# DRAM_DDR4_Bank_2_Connector.net
KiCad netlist of a schematic drawn in Altium Designer
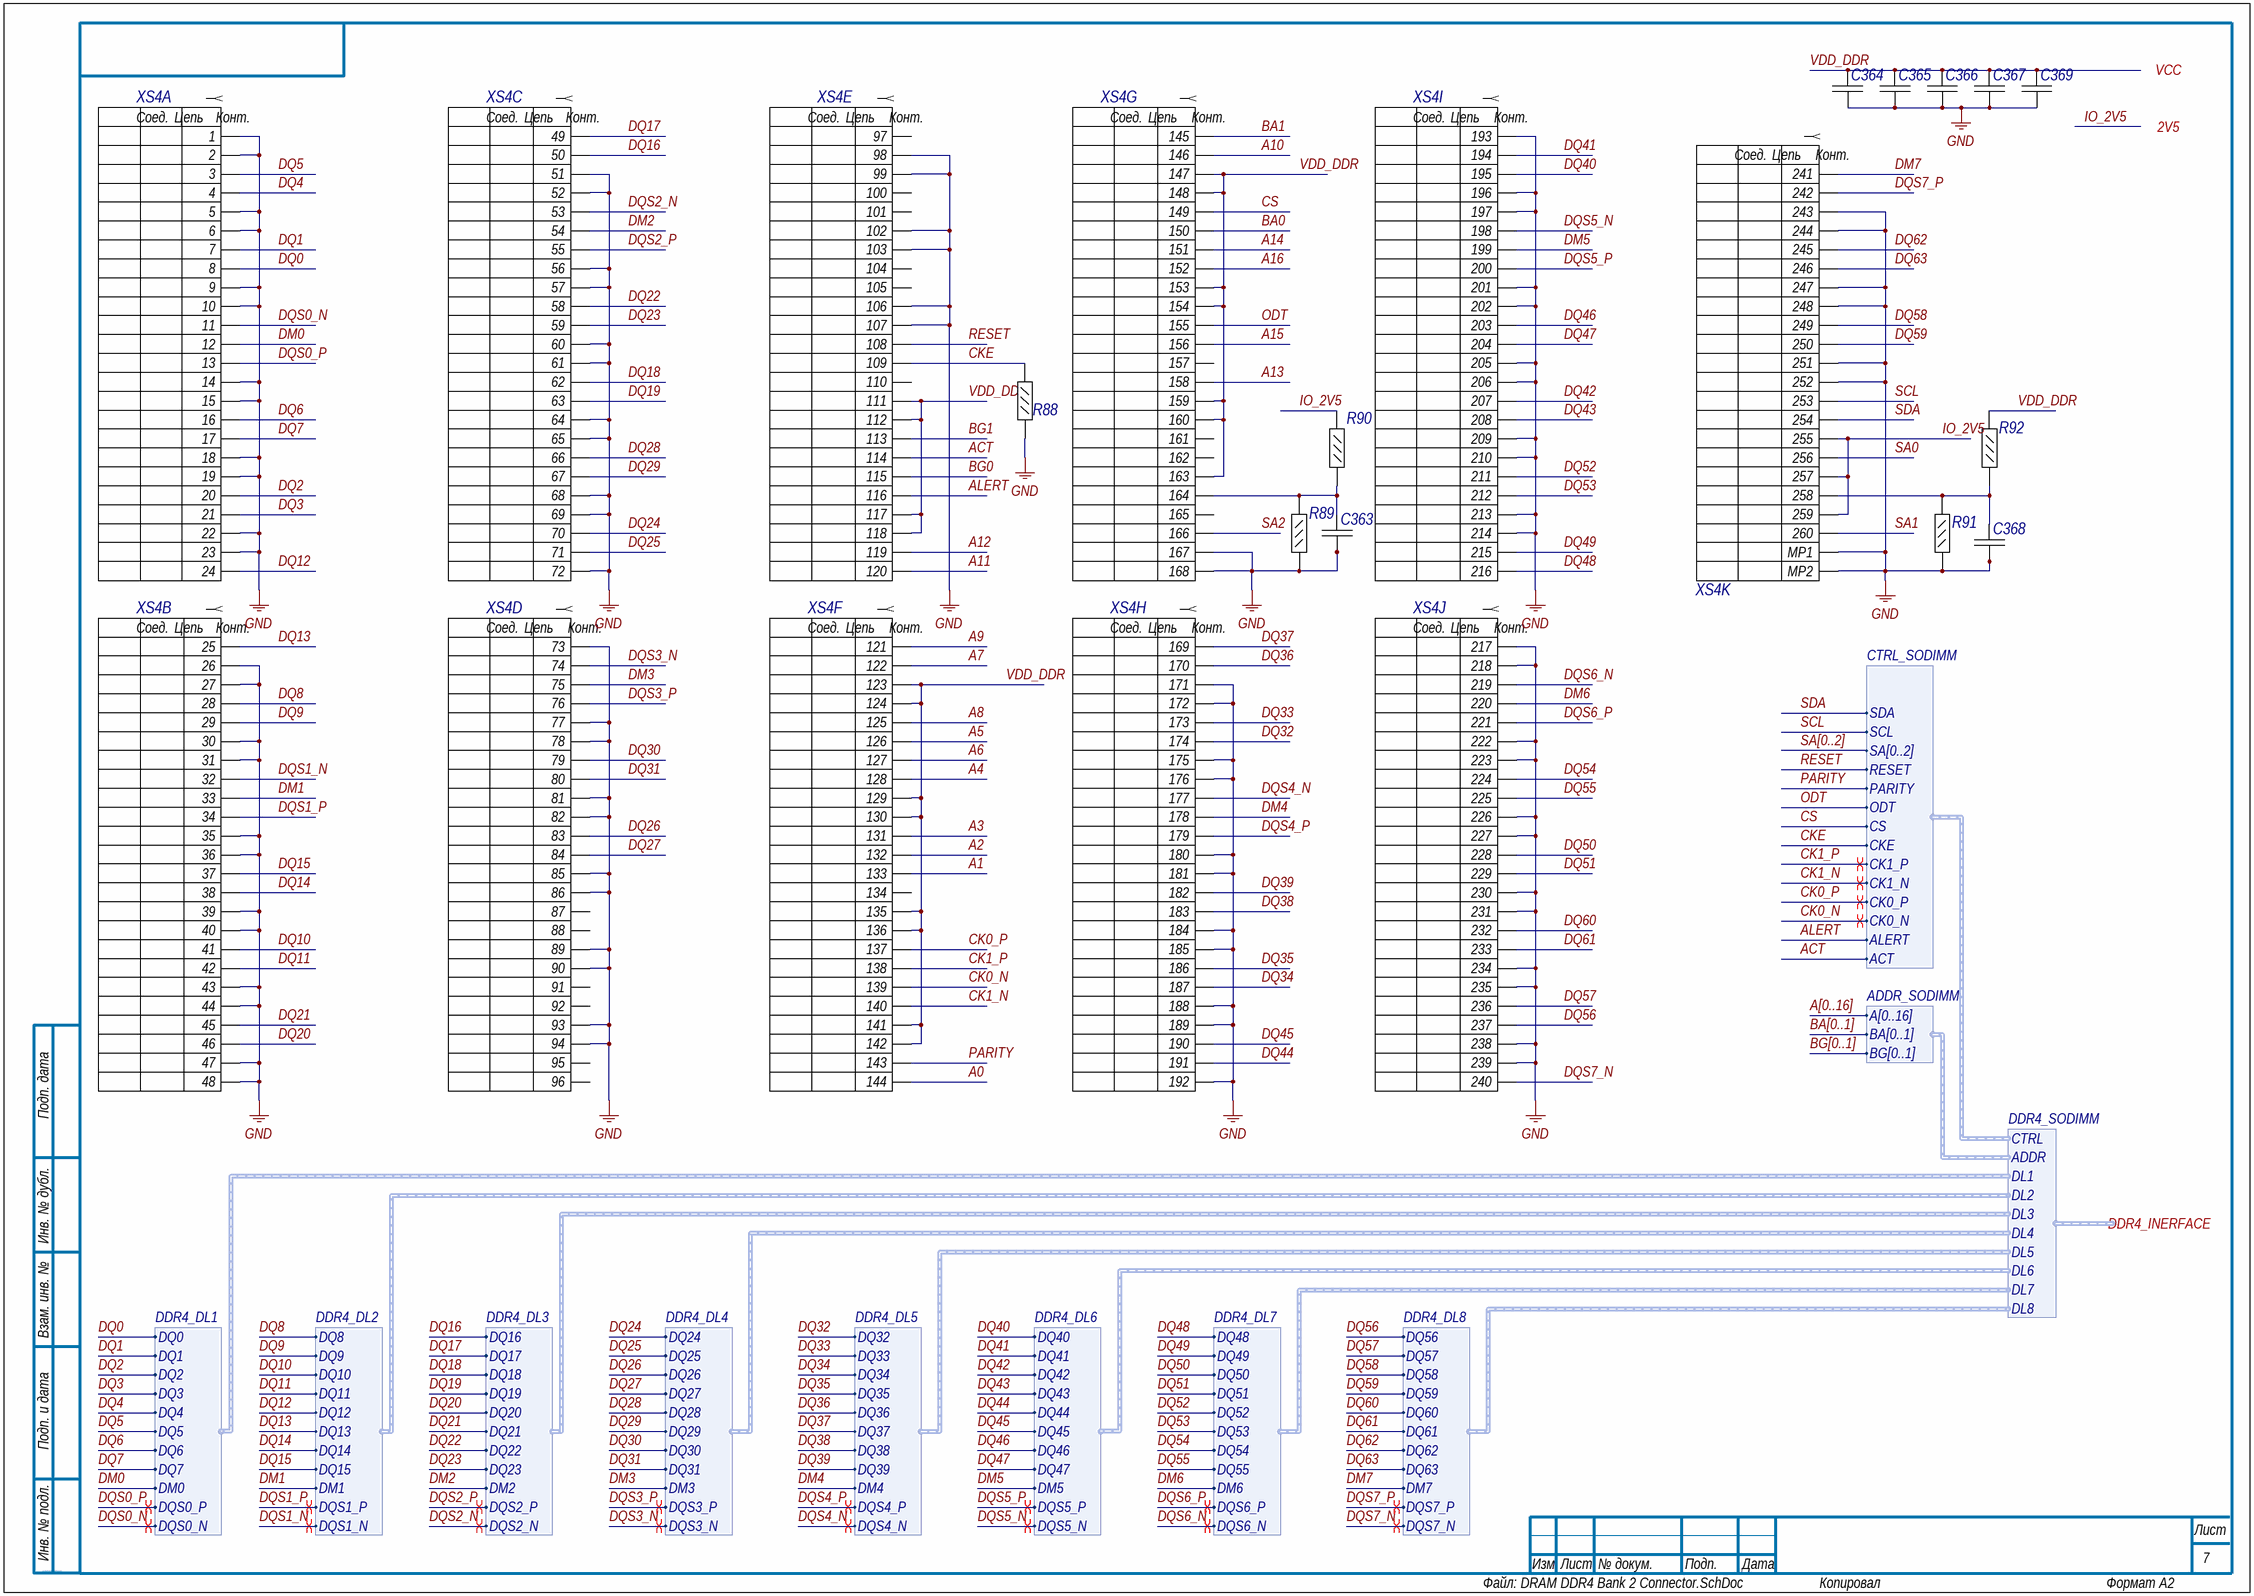
[diagram p0: DRAM DDR4 Bank 2 Connector.SchDoc]

(export (version "E")
  (design (tool "Eeschema 10.0.6"))
  (components
    (comp (ref "C363")
      (value "C1005X7R1E104M")
      (footprint "CAPC1005X55X10LL05")
      (description "Chip Capacitor, 0.1 uF, +/- 20%, 25 V, -55 to 125 degC, 0402 (1005 Metric), RoHS, Tape and Reel")
      (fields (field (name "TOLERANCE") "20%"))
      (libsource (lib "MiniPC DB") (part "CAP_NP"))
    )
    (comp (ref "C364")
      (value "C1005X7R1E104M")
      (footprint "CAPC1005X55X10LL05")
      (description "Chip Capacitor, 0.1 uF, +/- 20%, 25 V, -55 to 125 degC, 0402 (1005 Metric), RoHS, Tape and Reel")
      (fields (field (name "TOLERANCE") "20%"))
      (libsource (lib "MiniPC DB") (part "CAP_NP"))
    )
    (comp (ref "C365")
      (value "C1005X7R1E104M")
      (footprint "CAPC1005X55X10LL05")
      (description "Chip Capacitor, 0.1 uF, +/- 20%, 25 V, -55 to 125 degC, 0402 (1005 Metric), RoHS, Tape and Reel")
      (fields (field (name "TOLERANCE") "20%"))
      (libsource (lib "MiniPC DB") (part "CAP_NP"))
    )
    (comp (ref "C366")
      (value "C1005X7R1E104M")
      (footprint "CAPC1005X55X10LL05")
      (description "Chip Capacitor, 0.1 uF, +/- 20%, 25 V, -55 to 125 degC, 0402 (1005 Metric), RoHS, Tape and Reel")
      (fields (field (name "TOLERANCE") "20%"))
      (libsource (lib "MiniPC DB") (part "CAP_NP"))
    )
    (comp (ref "C367")
      (value "C1005X7R1E104M")
      (footprint "CAPC1005X55X10LL05")
      (description "Chip Capacitor, 0.1 uF, +/- 20%, 25 V, -55 to 125 degC, 0402 (1005 Metric), RoHS, Tape and Reel")
      (fields (field (name "TOLERANCE") "20%"))
      (libsource (lib "MiniPC DB") (part "CAP_NP"))
    )
    (comp (ref "C368")
      (value "C1005X7R1E104M")
      (footprint "CAPC1005X55X10LL05")
      (description "Chip Capacitor, 0.1 uF, +/- 20%, 25 V, -55 to 125 degC, 0402 (1005 Metric), RoHS, Tape and Reel")
      (fields (field (name "TOLERANCE") "20%"))
      (libsource (lib "MiniPC DB") (part "CAP_NP"))
    )
    (comp (ref "C369")
      (value "C1005X7R1E104M")
      (footprint "CAPC1005X55X10LL05")
      (description "Chip Capacitor, 0.1 uF, +/- 20%, 25 V, -55 to 125 degC, 0402 (1005 Metric), RoHS, Tape and Reel")
      (fields (field (name "TOLERANCE") "20%"))
      (libsource (lib "MiniPC DB") (part "CAP_NP"))
    )
    (comp (ref "R88")
      (value "RC0402JR-0739RL")
      (footprint "RESC1005X40X25LL05T05")
      (description "Chip Resistor, 39 Ohm, +/- 5%, 0.063 W, -55 to 155 degC, 0402 (1005 Metric), RoHS, Tape and Reel")
      (fields (field (name "TOLERANCE") "5%"))
      (libsource (lib "MiniPC DB") (part "RES-0.05"))
    )
    (comp (ref "R89")
      (value "RC0402JR-0739RL")
      (footprint "RESC1005X40X25LL05T05")
      (description "Chip Resistor, 39 Ohm, +/- 5%, 0.063 W, -55 to 155 degC, 0402 (1005 Metric), RoHS, Tape and Reel")
      (fields (field (name "TOLERANCE") "5%"))
      (libsource (lib "") (part "RES-0.05_1"))
    )
    (comp (ref "R90")
      (value "RC0402JR-0739RL")
      (footprint "RESC1005X40X25LL05T05")
      (description "Chip Resistor, 39 Ohm, +/- 5%, 0.063 W, -55 to 155 degC, 0402 (1005 Metric), RoHS, Tape and Reel")
      (fields (field (name "TOLERANCE") "5%"))
      (libsource (lib "") (part "RES-0.05_2"))
    )
    (comp (ref "R91")
      (value "RC0402JR-0739RL")
      (footprint "RESC1005X40X25LL05T05")
      (description "Chip Resistor, 39 Ohm, +/- 5%, 0.063 W, -55 to 155 degC, 0402 (1005 Metric), RoHS, Tape and Reel")
      (fields (field (name "TOLERANCE") "5%"))
      (libsource (lib "") (part "RES-0.05_1"))
    )
    (comp (ref "R92")
      (value "RC0402JR-0739RL")
      (footprint "RESC1005X40X25LL05T05")
      (description "Chip Resistor, 39 Ohm, +/- 5%, 0.063 W, -55 to 155 degC, 0402 (1005 Metric), RoHS, Tape and Reel")
      (fields (field (name "TOLERANCE") "5%"))
      (libsource (lib "") (part "RES-0.05_2"))
    )
    (comp (ref "XS4")
      (value "AS0A823-H4SB-7H")
      (footprint "FOXC-AS0A823-H4SB-7H_V")
      (libsource (lib "MiniPC DB") (part "ROZ_262K"))
    )
  )
  (nets
    (net (code "10") (name "/A0") (class "Default")
      (node (ref "XS4") (pin "144") (pinfunction "144_144") (pintype "passive"))
    )
    (net (code "11") (name "/A1") (class "Default")
      (node (ref "XS4") (pin "133") (pinfunction "133_133") (pintype "passive"))
    )
    (net (code "12") (name "/A2") (class "Default")
      (node (ref "XS4") (pin "132") (pinfunction "132_132") (pintype "passive"))
    )
    (net (code "13") (name "/A3") (class "Default")
      (node (ref "XS4") (pin "131") (pinfunction "131_131") (pintype "passive"))
    )
    (net (code "14") (name "/A4") (class "Default")
      (node (ref "XS4") (pin "128") (pinfunction "128_128") (pintype "passive"))
    )
    (net (code "15") (name "/A5") (class "Default")
      (node (ref "XS4") (pin "126") (pinfunction "126_126") (pintype "passive"))
    )
    (net (code "16") (name "/A6") (class "Default")
      (node (ref "XS4") (pin "127") (pinfunction "127_127") (pintype "passive"))
    )
    (net (code "17") (name "/A7") (class "Default")
      (node (ref "XS4") (pin "122") (pinfunction "122_122") (pintype "passive"))
    )
    (net (code "18") (name "/A8") (class "Default")
      (node (ref "XS4") (pin "125") (pinfunction "125_125") (pintype "passive"))
    )
    (net (code "19") (name "/A9") (class "Default")
      (node (ref "XS4") (pin "121") (pinfunction "121_121") (pintype "passive"))
    )
    (net (code "20") (name "/A10") (class "Default")
      (node (ref "XS4") (pin "146") (pinfunction "146_146") (pintype "passive"))
    )
    (net (code "21") (name "/A11") (class "Default")
      (node (ref "XS4") (pin "120") (pinfunction "120_120") (pintype "passive"))
    )
    (net (code "22") (name "/A12") (class "Default")
      (node (ref "XS4") (pin "119") (pinfunction "119_119") (pintype "passive"))
    )
    (net (code "23") (name "/A13") (class "Default")
      (node (ref "XS4") (pin "158") (pinfunction "158_158") (pintype "passive"))
    )
    (net (code "24") (name "/A14") (class "Default")
      (node (ref "XS4") (pin "151") (pinfunction "151_151") (pintype "passive"))
    )
    (net (code "25") (name "/A15") (class "Default")
      (node (ref "XS4") (pin "156") (pinfunction "156_156") (pintype "passive"))
    )
    (net (code "26") (name "/A16") (class "Default")
      (node (ref "XS4") (pin "152") (pinfunction "152_152") (pintype "passive"))
    )
    (net (code "27") (name "/ACT") (class "Default")
      (node (ref "XS4") (pin "114") (pinfunction "114_114") (pintype "passive"))
    )
    (net (code "28") (name "/ALERT") (class "Default")
      (node (ref "XS4") (pin "116") (pinfunction "116_116") (pintype "passive"))
    )
    (net (code "30") (name "/BA0") (class "Default")
      (node (ref "XS4") (pin "150") (pinfunction "150_150") (pintype "passive"))
    )
    (net (code "31") (name "/BA1") (class "Default")
      (node (ref "XS4") (pin "145") (pinfunction "145_145") (pintype "passive"))
    )
    (net (code "33") (name "/BG0") (class "Default")
      (node (ref "XS4") (pin "115") (pinfunction "115_115") (pintype "passive"))
    )
    (net (code "34") (name "/BG1") (class "Default")
      (node (ref "XS4") (pin "113") (pinfunction "113_113") (pintype "passive"))
    )
    (net (code "35") (name "/CK0_N") (class "Default")
      (node (ref "XS4") (pin "139") (pinfunction "139_139") (pintype "passive"))
    )
    (net (code "36") (name "/CK0_P") (class "Default")
      (node (ref "XS4") (pin "137") (pinfunction "137_137") (pintype "passive"))
    )
    (net (code "37") (name "/CK1_N") (class "Default")
      (node (ref "XS4") (pin "140") (pinfunction "140_140") (pintype "passive"))
    )
    (net (code "38") (name "/CK1_P") (class "Default")
      (node (ref "XS4") (pin "138") (pinfunction "138_138") (pintype "passive"))
    )
    (net (code "39") (name "/CKE") (class "Default")
      (node (ref "R88") (pin "2") (pinfunction "2_2") (pintype "passive"))
      (node (ref "XS4") (pin "109") (pinfunction "109_109") (pintype "passive"))
    )
    (net (code "40") (name "/CS") (class "Default")
      (node (ref "XS4") (pin "149") (pinfunction "149_149") (pintype "passive"))
    )
    (net (code "42") (name "/DM0") (class "Default")
      (node (ref "XS4") (pin "12") (pinfunction "12_12") (pintype "passive"))
    )
    (net (code "43") (name "/DM1") (class "Default")
      (node (ref "XS4") (pin "33") (pinfunction "33_33") (pintype "passive"))
    )
    (net (code "44") (name "/DM2") (class "Default")
      (node (ref "XS4") (pin "54") (pinfunction "54_54") (pintype "passive"))
    )
    (net (code "45") (name "/DM3") (class "Default")
      (node (ref "XS4") (pin "75") (pinfunction "75_75") (pintype "passive"))
    )
    (net (code "46") (name "/DM4") (class "Default")
      (node (ref "XS4") (pin "178") (pinfunction "178_178") (pintype "passive"))
    )
    (net (code "47") (name "/DM5") (class "Default")
      (node (ref "XS4") (pin "199") (pinfunction "199_199") (pintype "passive"))
    )
    (net (code "48") (name "/DM6") (class "Default")
      (node (ref "XS4") (pin "220") (pinfunction "220_220") (pintype "passive"))
    )
    (net (code "49") (name "/DM7") (class "Default")
      (node (ref "XS4") (pin "241") (pinfunction "241_241") (pintype "passive"))
    )
    (net (code "50") (name "/DQ0") (class "Default")
      (node (ref "XS4") (pin "8") (pinfunction "8_8") (pintype "passive"))
    )
    (net (code "51") (name "/DQ1") (class "Default")
      (node (ref "XS4") (pin "7") (pinfunction "7_7") (pintype "passive"))
    )
    (net (code "52") (name "/DQ2") (class "Default")
      (node (ref "XS4") (pin "20") (pinfunction "20_20") (pintype "passive"))
    )
    (net (code "53") (name "/DQ3") (class "Default")
      (node (ref "XS4") (pin "21") (pinfunction "21_21") (pintype "passive"))
    )
    (net (code "54") (name "/DQ4") (class "Default")
      (node (ref "XS4") (pin "4") (pinfunction "4_4") (pintype "passive"))
    )
    (net (code "55") (name "/DQ5") (class "Default")
      (node (ref "XS4") (pin "3") (pinfunction "3_3") (pintype "passive"))
    )
    (net (code "56") (name "/DQ6") (class "Default")
      (node (ref "XS4") (pin "16") (pinfunction "16_16") (pintype "passive"))
    )
    (net (code "57") (name "/DQ7") (class "Default")
      (node (ref "XS4") (pin "17") (pinfunction "17_17") (pintype "passive"))
    )
    (net (code "58") (name "/DQ8") (class "Default")
      (node (ref "XS4") (pin "28") (pinfunction "28_28") (pintype "passive"))
    )
    (net (code "59") (name "/DQ9") (class "Default")
      (node (ref "XS4") (pin "29") (pinfunction "29_29") (pintype "passive"))
    )
    (net (code "60") (name "/DQ10") (class "Default")
      (node (ref "XS4") (pin "41") (pinfunction "41_41") (pintype "passive"))
    )
    (net (code "61") (name "/DQ11") (class "Default")
      (node (ref "XS4") (pin "42") (pinfunction "42_42") (pintype "passive"))
    )
    (net (code "62") (name "/DQ12") (class "Default")
      (node (ref "XS4") (pin "24") (pinfunction "24_24") (pintype "passive"))
    )
    (net (code "63") (name "/DQ13") (class "Default")
      (node (ref "XS4") (pin "25") (pinfunction "25_25") (pintype "passive"))
    )
    (net (code "64") (name "/DQ14") (class "Default")
      (node (ref "XS4") (pin "38") (pinfunction "38_38") (pintype "passive"))
    )
    (net (code "65") (name "/DQ15") (class "Default")
      (node (ref "XS4") (pin "37") (pinfunction "37_37") (pintype "passive"))
    )
    (net (code "66") (name "/DQ16") (class "Default")
      (node (ref "XS4") (pin "50") (pinfunction "50_50") (pintype "passive"))
    )
    (net (code "67") (name "/DQ17") (class "Default")
      (node (ref "XS4") (pin "49") (pinfunction "49_49") (pintype "passive"))
    )
    (net (code "68") (name "/DQ18") (class "Default")
      (node (ref "XS4") (pin "62") (pinfunction "62_62") (pintype "passive"))
    )
    (net (code "69") (name "/DQ19") (class "Default")
      (node (ref "XS4") (pin "63") (pinfunction "63_63") (pintype "passive"))
    )
    (net (code "70") (name "/DQ20") (class "Default")
      (node (ref "XS4") (pin "46") (pinfunction "46_46") (pintype "passive"))
    )
    (net (code "71") (name "/DQ21") (class "Default")
      (node (ref "XS4") (pin "45") (pinfunction "45_45") (pintype "passive"))
    )
    (net (code "72") (name "/DQ22") (class "Default")
      (node (ref "XS4") (pin "58") (pinfunction "58_58") (pintype "passive"))
    )
    (net (code "73") (name "/DQ23") (class "Default")
      (node (ref "XS4") (pin "59") (pinfunction "59_59") (pintype "passive"))
    )
    (net (code "74") (name "/DQ24") (class "Default")
      (node (ref "XS4") (pin "70") (pinfunction "70_70") (pintype "passive"))
    )
    (net (code "75") (name "/DQ25") (class "Default")
      (node (ref "XS4") (pin "71") (pinfunction "71_71") (pintype "passive"))
    )
    (net (code "76") (name "/DQ26") (class "Default")
      (node (ref "XS4") (pin "83") (pinfunction "83_83") (pintype "passive"))
    )
    (net (code "77") (name "/DQ27") (class "Default")
      (node (ref "XS4") (pin "84") (pinfunction "84_84") (pintype "passive"))
    )
    (net (code "78") (name "/DQ28") (class "Default")
      (node (ref "XS4") (pin "66") (pinfunction "66_66") (pintype "passive"))
    )
    (net (code "79") (name "/DQ29") (class "Default")
      (node (ref "XS4") (pin "67") (pinfunction "67_67") (pintype "passive"))
    )
    (net (code "80") (name "/DQ30") (class "Default")
      (node (ref "XS4") (pin "79") (pinfunction "79_79") (pintype "passive"))
    )
    (net (code "81") (name "/DQ31") (class "Default")
      (node (ref "XS4") (pin "80") (pinfunction "80_80") (pintype "passive"))
    )
    (net (code "82") (name "/DQ32") (class "Default")
      (node (ref "XS4") (pin "174") (pinfunction "174_174") (pintype "passive"))
    )
    (net (code "83") (name "/DQ33") (class "Default")
      (node (ref "XS4") (pin "173") (pinfunction "173_173") (pintype "passive"))
    )
    (net (code "84") (name "/DQ34") (class "Default")
      (node (ref "XS4") (pin "187") (pinfunction "187_187") (pintype "passive"))
    )
    (net (code "85") (name "/DQ35") (class "Default")
      (node (ref "XS4") (pin "186") (pinfunction "186_186") (pintype "passive"))
    )
    (net (code "86") (name "/DQ36") (class "Default")
      (node (ref "XS4") (pin "170") (pinfunction "170_170") (pintype "passive"))
    )
    (net (code "87") (name "/DQ37") (class "Default")
      (node (ref "XS4") (pin "169") (pinfunction "169_169") (pintype "passive"))
    )
    (net (code "88") (name "/DQ38") (class "Default")
      (node (ref "XS4") (pin "183") (pinfunction "183_183") (pintype "passive"))
    )
    (net (code "89") (name "/DQ39") (class "Default")
      (node (ref "XS4") (pin "182") (pinfunction "182_182") (pintype "passive"))
    )
    (net (code "90") (name "/DQ40") (class "Default")
      (node (ref "XS4") (pin "195") (pinfunction "195_195") (pintype "passive"))
    )
    (net (code "91") (name "/DQ41") (class "Default")
      (node (ref "XS4") (pin "194") (pinfunction "194_194") (pintype "passive"))
    )
    (net (code "92") (name "/DQ42") (class "Default")
      (node (ref "XS4") (pin "207") (pinfunction "207_207") (pintype "passive"))
    )
    (net (code "93") (name "/DQ43") (class "Default")
      (node (ref "XS4") (pin "208") (pinfunction "208_208") (pintype "passive"))
    )
    (net (code "94") (name "/DQ44") (class "Default")
      (node (ref "XS4") (pin "191") (pinfunction "191_191") (pintype "passive"))
    )
    (net (code "95") (name "/DQ45") (class "Default")
      (node (ref "XS4") (pin "190") (pinfunction "190_190") (pintype "passive"))
    )
    (net (code "96") (name "/DQ46") (class "Default")
      (node (ref "XS4") (pin "203") (pinfunction "203_203") (pintype "passive"))
    )
    (net (code "97") (name "/DQ47") (class "Default")
      (node (ref "XS4") (pin "204") (pinfunction "204_204") (pintype "passive"))
    )
    (net (code "98") (name "/DQ48") (class "Default")
      (node (ref "XS4") (pin "216") (pinfunction "216_216") (pintype "passive"))
    )
    (net (code "99") (name "/DQ49") (class "Default")
      (node (ref "XS4") (pin "215") (pinfunction "215_215") (pintype "passive"))
    )
    (net (code "100") (name "/DQ50") (class "Default")
      (node (ref "XS4") (pin "228") (pinfunction "228_228") (pintype "passive"))
    )
    (net (code "101") (name "/DQ51") (class "Default")
      (node (ref "XS4") (pin "229") (pinfunction "229_229") (pintype "passive"))
    )
    (net (code "102") (name "/DQ52") (class "Default")
      (node (ref "XS4") (pin "211") (pinfunction "211_211") (pintype "passive"))
    )
    (net (code "103") (name "/DQ53") (class "Default")
      (node (ref "XS4") (pin "212") (pinfunction "212_212") (pintype "passive"))
    )
    (net (code "104") (name "/DQ54") (class "Default")
      (node (ref "XS4") (pin "224") (pinfunction "224_224") (pintype "passive"))
    )
    (net (code "105") (name "/DQ55") (class "Default")
      (node (ref "XS4") (pin "225") (pinfunction "225_225") (pintype "passive"))
    )
    (net (code "106") (name "/DQ56") (class "Default")
      (node (ref "XS4") (pin "237") (pinfunction "237_237") (pintype "passive"))
    )
    (net (code "107") (name "/DQ57") (class "Default")
      (node (ref "XS4") (pin "236") (pinfunction "236_236") (pintype "passive"))
    )
    (net (code "108") (name "/DQ58") (class "Default")
      (node (ref "XS4") (pin "249") (pinfunction "249_249") (pintype "passive"))
    )
    (net (code "109") (name "/DQ59") (class "Default")
      (node (ref "XS4") (pin "250") (pinfunction "250_250") (pintype "passive"))
    )
    (net (code "110") (name "/DQ60") (class "Default")
      (node (ref "XS4") (pin "232") (pinfunction "232_232") (pintype "passive"))
    )
    (net (code "111") (name "/DQ61") (class "Default")
      (node (ref "XS4") (pin "233") (pinfunction "233_233") (pintype "passive"))
    )
    (net (code "112") (name "/DQ62") (class "Default")
      (node (ref "XS4") (pin "245") (pinfunction "245_245") (pintype "passive"))
    )
    (net (code "113") (name "/DQ63") (class "Default")
      (node (ref "XS4") (pin "246") (pinfunction "246_246") (pintype "passive"))
    )
    (net (code "114") (name "/DQS0_N") (class "Default")
      (node (ref "XS4") (pin "11") (pinfunction "11_11") (pintype "passive"))
    )
    (net (code "115") (name "/DQS0_P") (class "Default")
      (node (ref "XS4") (pin "13") (pinfunction "13_13") (pintype "passive"))
    )
    (net (code "116") (name "/DQS1_N") (class "Default")
      (node (ref "XS4") (pin "32") (pinfunction "32_32") (pintype "passive"))
    )
    (net (code "117") (name "/DQS1_P") (class "Default")
      (node (ref "XS4") (pin "34") (pinfunction "34_34") (pintype "passive"))
    )
    (net (code "118") (name "/DQS2_N") (class "Default")
      (node (ref "XS4") (pin "53") (pinfunction "53_53") (pintype "passive"))
    )
    (net (code "119") (name "/DQS2_P") (class "Default")
      (node (ref "XS4") (pin "55") (pinfunction "55_55") (pintype "passive"))
    )
    (net (code "120") (name "/DQS3_N") (class "Default")
      (node (ref "XS4") (pin "74") (pinfunction "74_74") (pintype "passive"))
    )
    (net (code "121") (name "/DQS3_P") (class "Default")
      (node (ref "XS4") (pin "76") (pinfunction "76_76") (pintype "passive"))
    )
    (net (code "122") (name "/DQS4_N") (class "Default")
      (node (ref "XS4") (pin "177") (pinfunction "177_177") (pintype "passive"))
    )
    (net (code "123") (name "/DQS4_P") (class "Default")
      (node (ref "XS4") (pin "179") (pinfunction "179_179") (pintype "passive"))
    )
    (net (code "124") (name "/DQS5_N") (class "Default")
      (node (ref "XS4") (pin "198") (pinfunction "198_198") (pintype "passive"))
    )
    (net (code "125") (name "/DQS5_P") (class "Default")
      (node (ref "XS4") (pin "200") (pinfunction "200_200") (pintype "passive"))
    )
    (net (code "126") (name "/DQS6_N") (class "Default")
      (node (ref "XS4") (pin "219") (pinfunction "219_219") (pintype "passive"))
    )
    (net (code "127") (name "/DQS6_P") (class "Default")
      (node (ref "XS4") (pin "221") (pinfunction "221_221") (pintype "passive"))
    )
    (net (code "128") (name "/DQS7_N") (class "Default")
      (node (ref "XS4") (pin "240") (pinfunction "240_240") (pintype "passive"))
    )
    (net (code "129") (name "/DQS7_P") (class "Default")
      (node (ref "XS4") (pin "242") (pinfunction "242_242") (pintype "passive"))
    )
    (net (code "130") (name "/IO_2V5") (class "Default")
      (node (ref "R90") (pin "1") (pinfunction "1_1") (pintype "passive"))
      (node (ref "XS4") (pin "255") (pinfunction "255_255") (pintype "passive"))
      (node (ref "XS4") (pin "257") (pinfunction "257_257") (pintype "passive"))
      (node (ref "XS4") (pin "259") (pinfunction "259_259") (pintype "passive"))
    )
    (net (code "131") (name "/ODT") (class "Default")
      (node (ref "XS4") (pin "155") (pinfunction "155_155") (pintype "passive"))
    )
    (net (code "132") (name "/PARITY") (class "Default")
      (node (ref "XS4") (pin "143") (pinfunction "143_143") (pintype "passive"))
    )
    (net (code "133") (name "/RESET") (class "Default")
      (node (ref "XS4") (pin "108") (pinfunction "108_108") (pintype "passive"))
    )
    (net (code "134") (name "/SA0") (class "Default")
      (node (ref "XS4") (pin "256") (pinfunction "256_256") (pintype "passive"))
    )
    (net (code "135") (name "/SA1") (class "Default")
      (node (ref "XS4") (pin "260") (pinfunction "260_260") (pintype "passive"))
    )
    (net (code "136") (name "/SA2") (class "Default")
      (node (ref "XS4") (pin "166") (pinfunction "166_166") (pintype "passive"))
    )
    (net (code "137") (name "/SCL") (class "Default")
      (node (ref "XS4") (pin "253") (pinfunction "253_253") (pintype "passive"))
    )
    (net (code "138") (name "/SDA") (class "Default")
      (node (ref "XS4") (pin "254") (pinfunction "254_254") (pintype "passive"))
    )
    (net (code "139") (name "/VDD_DDR") (class "Default")
      (node (ref "C364") (pin "1") (pinfunction "1_1") (pintype "passive"))
      (node (ref "C365") (pin "1") (pinfunction "1_1") (pintype "passive"))
      (node (ref "C366") (pin "1") (pinfunction "1_1") (pintype "passive"))
      (node (ref "C367") (pin "1") (pinfunction "1_1") (pintype "passive"))
      (node (ref "C369") (pin "1") (pinfunction "1_1") (pintype "passive"))
      (node (ref "R92") (pin "1") (pinfunction "1_1") (pintype "passive"))
      (node (ref "XS4") (pin "111") (pinfunction "111_111") (pintype "passive"))
      (node (ref "XS4") (pin "112") (pinfunction "112_112") (pintype "passive"))
      (node (ref "XS4") (pin "117") (pinfunction "117_117") (pintype "passive"))
      (node (ref "XS4") (pin "118") (pinfunction "118_118") (pintype "passive"))
      (node (ref "XS4") (pin "123") (pinfunction "123_123") (pintype "passive"))
      (node (ref "XS4") (pin "124") (pinfunction "124_124") (pintype "passive"))
      (node (ref "XS4") (pin "129") (pinfunction "129_129") (pintype "passive"))
      (node (ref "XS4") (pin "130") (pinfunction "130_130") (pintype "passive"))
      (node (ref "XS4") (pin "135") (pinfunction "135_135") (pintype "passive"))
      (node (ref "XS4") (pin "136") (pinfunction "136_136") (pintype "passive"))
      (node (ref "XS4") (pin "141") (pinfunction "141_141") (pintype "passive"))
      (node (ref "XS4") (pin "142") (pinfunction "142_142") (pintype "passive"))
      (node (ref "XS4") (pin "147") (pinfunction "147_147") (pintype "passive"))
      (node (ref "XS4") (pin "148") (pinfunction "148_148") (pintype "passive"))
      (node (ref "XS4") (pin "153") (pinfunction "153_153") (pintype "passive"))
      (node (ref "XS4") (pin "154") (pinfunction "154_154") (pintype "passive"))
      (node (ref "XS4") (pin "159") (pinfunction "159_159") (pintype "passive"))
      (node (ref "XS4") (pin "160") (pinfunction "160_160") (pintype "passive"))
      (node (ref "XS4") (pin "163") (pinfunction "163_163") (pintype "passive"))
    )
    (net (code "150") (name "GND") (class "Default")
      (node (ref "C363") (pin "2") (pinfunction "2_2") (pintype "passive"))
      (node (ref "C364") (pin "2") (pinfunction "2_2") (pintype "passive"))
      (node (ref "C365") (pin "2") (pinfunction "2_2") (pintype "passive"))
      (node (ref "C366") (pin "2") (pinfunction "2_2") (pintype "passive"))
      (node (ref "C367") (pin "2") (pinfunction "2_2") (pintype "passive"))
      (node (ref "C368") (pin "2") (pinfunction "2_2") (pintype "passive"))
      (node (ref "C369") (pin "2") (pinfunction "2_2") (pintype "passive"))
      (node (ref "R88") (pin "1") (pinfunction "1_1") (pintype "passive"))
      (node (ref "R89") (pin "1") (pinfunction "1_1") (pintype "passive"))
      (node (ref "R91") (pin "1") (pinfunction "1_1") (pintype "passive"))
      (node (ref "XS4") (pin "1") (pinfunction "1_1") (pintype "passive"))
      (node (ref "XS4") (pin "10") (pinfunction "10_10") (pintype "passive"))
      (node (ref "XS4") (pin "102") (pinfunction "102_102") (pintype "passive"))
      (node (ref "XS4") (pin "103") (pinfunction "103_103") (pintype "passive"))
      (node (ref "XS4") (pin "106") (pinfunction "106_106") (pintype "passive"))
      (node (ref "XS4") (pin "107") (pinfunction "107_107") (pintype "passive"))
      (node (ref "XS4") (pin "14") (pinfunction "14_14") (pintype "passive"))
      (node (ref "XS4") (pin "15") (pinfunction "15_15") (pintype "passive"))
      (node (ref "XS4") (pin "167") (pinfunction "167_167") (pintype "passive"))
      (node (ref "XS4") (pin "168") (pinfunction "168_168") (pintype "passive"))
      (node (ref "XS4") (pin "171") (pinfunction "171_171") (pintype "passive"))
      (node (ref "XS4") (pin "172") (pinfunction "172_172") (pintype "passive"))
      (node (ref "XS4") (pin "175") (pinfunction "175_175") (pintype "passive"))
      (node (ref "XS4") (pin "176") (pinfunction "176_176") (pintype "passive"))
      (node (ref "XS4") (pin "18") (pinfunction "18_18") (pintype "passive"))
      (node (ref "XS4") (pin "180") (pinfunction "180_180") (pintype "passive"))
      (node (ref "XS4") (pin "181") (pinfunction "181_181") (pintype "passive"))
      (node (ref "XS4") (pin "184") (pinfunction "184_184") (pintype "passive"))
      (node (ref "XS4") (pin "185") (pinfunction "185_185") (pintype "passive"))
      (node (ref "XS4") (pin "188") (pinfunction "188_188") (pintype "passive"))
      (node (ref "XS4") (pin "189") (pinfunction "189_189") (pintype "passive"))
      (node (ref "XS4") (pin "19") (pinfunction "19_19") (pintype "passive"))
      (node (ref "XS4") (pin "192") (pinfunction "192_192") (pintype "passive"))
      (node (ref "XS4") (pin "193") (pinfunction "193_193") (pintype "passive"))
      (node (ref "XS4") (pin "196") (pinfunction "196_196") (pintype "passive"))
      (node (ref "XS4") (pin "197") (pinfunction "197_197") (pintype "passive"))
      (node (ref "XS4") (pin "2") (pinfunction "2_2") (pintype "passive"))
      (node (ref "XS4") (pin "201") (pinfunction "201_201") (pintype "passive"))
      (node (ref "XS4") (pin "202") (pinfunction "202_202") (pintype "passive"))
      (node (ref "XS4") (pin "205") (pinfunction "205_205") (pintype "passive"))
      (node (ref "XS4") (pin "206") (pinfunction "206_206") (pintype "passive"))
      (node (ref "XS4") (pin "209") (pinfunction "209_209") (pintype "passive"))
      (node (ref "XS4") (pin "210") (pinfunction "210_210") (pintype "passive"))
      (node (ref "XS4") (pin "213") (pinfunction "213_213") (pintype "passive"))
      (node (ref "XS4") (pin "214") (pinfunction "214_214") (pintype "passive"))
      (node (ref "XS4") (pin "217") (pinfunction "217_217") (pintype "passive"))
      (node (ref "XS4") (pin "218") (pinfunction "218_218") (pintype "passive"))
      (node (ref "XS4") (pin "22") (pinfunction "22_22") (pintype "passive"))
      (node (ref "XS4") (pin "222") (pinfunction "222_222") (pintype "passive"))
      (node (ref "XS4") (pin "223") (pinfunction "223_223") (pintype "passive"))
      (node (ref "XS4") (pin "226") (pinfunction "226_226") (pintype "passive"))
      (node (ref "XS4") (pin "227") (pinfunction "227_227") (pintype "passive"))
      (node (ref "XS4") (pin "23") (pinfunction "23_23") (pintype "passive"))
      (node (ref "XS4") (pin "230") (pinfunction "230_230") (pintype "passive"))
      (node (ref "XS4") (pin "231") (pinfunction "231_231") (pintype "passive"))
      (node (ref "XS4") (pin "234") (pinfunction "234_234") (pintype "passive"))
      (node (ref "XS4") (pin "235") (pinfunction "235_235") (pintype "passive"))
      (node (ref "XS4") (pin "238") (pinfunction "238_238") (pintype "passive"))
      (node (ref "XS4") (pin "239") (pinfunction "239_239") (pintype "passive"))
      (node (ref "XS4") (pin "243") (pinfunction "243_243") (pintype "passive"))
      (node (ref "XS4") (pin "244") (pinfunction "244_244") (pintype "passive"))
      (node (ref "XS4") (pin "247") (pinfunction "247_247") (pintype "passive"))
      (node (ref "XS4") (pin "248") (pinfunction "248_248") (pintype "passive"))
      (node (ref "XS4") (pin "251") (pinfunction "251_251") (pintype "passive"))
      (node (ref "XS4") (pin "252") (pinfunction "252_252") (pintype "passive"))
      (node (ref "XS4") (pin "26") (pinfunction "26_26") (pintype "passive"))
      (node (ref "XS4") (pin "27") (pinfunction "27_27") (pintype "passive"))
      (node (ref "XS4") (pin "30") (pinfunction "30_30") (pintype "passive"))
      (node (ref "XS4") (pin "31") (pinfunction "31_31") (pintype "passive"))
      (node (ref "XS4") (pin "35") (pinfunction "35_35") (pintype "passive"))
      (node (ref "XS4") (pin "36") (pinfunction "36_36") (pintype "passive"))
      (node (ref "XS4") (pin "39") (pinfunction "39_39") (pintype "passive"))
      (node (ref "XS4") (pin "40") (pinfunction "40_40") (pintype "passive"))
      (node (ref "XS4") (pin "43") (pinfunction "43_43") (pintype "passive"))
      (node (ref "XS4") (pin "44") (pinfunction "44_44") (pintype "passive"))
      (node (ref "XS4") (pin "47") (pinfunction "47_47") (pintype "passive"))
      (node (ref "XS4") (pin "48") (pinfunction "48_48") (pintype "passive"))
      (node (ref "XS4") (pin "5") (pinfunction "5_5") (pintype "passive"))
      (node (ref "XS4") (pin "51") (pinfunction "51_51") (pintype "passive"))
      (node (ref "XS4") (pin "52") (pinfunction "52_52") (pintype "passive"))
      (node (ref "XS4") (pin "56") (pinfunction "56_56") (pintype "passive"))
      (node (ref "XS4") (pin "57") (pinfunction "57_57") (pintype "passive"))
      (node (ref "XS4") (pin "6") (pinfunction "6_6") (pintype "passive"))
      (node (ref "XS4") (pin "60") (pinfunction "60_60") (pintype "passive"))
      (node (ref "XS4") (pin "61") (pinfunction "61_61") (pintype "passive"))
      (node (ref "XS4") (pin "64") (pinfunction "64_64") (pintype "passive"))
      (node (ref "XS4") (pin "65") (pinfunction "65_65") (pintype "passive"))
      (node (ref "XS4") (pin "68") (pinfunction "68_68") (pintype "passive"))
      (node (ref "XS4") (pin "69") (pinfunction "69_69") (pintype "passive"))
      (node (ref "XS4") (pin "72") (pinfunction "72_72") (pintype "passive"))
      (node (ref "XS4") (pin "73") (pinfunction "73_73") (pintype "passive"))
      (node (ref "XS4") (pin "77") (pinfunction "77_77") (pintype "passive"))
      (node (ref "XS4") (pin "78") (pinfunction "78_78") (pintype "passive"))
      (node (ref "XS4") (pin "81") (pinfunction "81_81") (pintype "passive"))
      (node (ref "XS4") (pin "82") (pinfunction "82_82") (pintype "passive"))
      (node (ref "XS4") (pin "85") (pinfunction "85_85") (pintype "passive"))
      (node (ref "XS4") (pin "86") (pinfunction "86_86") (pintype "passive"))
      (node (ref "XS4") (pin "89") (pinfunction "89_89") (pintype "passive"))
      (node (ref "XS4") (pin "9") (pinfunction "9_9") (pintype "passive"))
      (node (ref "XS4") (pin "90") (pinfunction "90_90") (pintype "passive"))
      (node (ref "XS4") (pin "93") (pinfunction "93_93") (pintype "passive"))
      (node (ref "XS4") (pin "94") (pinfunction "94_94") (pintype "passive"))
      (node (ref "XS4") (pin "98") (pinfunction "98_98") (pintype "passive"))
      (node (ref "XS4") (pin "99") (pinfunction "99_99") (pintype "passive"))
      (node (ref "XS4") (pin "MP1") (pinfunction "MP1_MP1") (pintype "passive"))
      (node (ref "XS4") (pin "MP2") (pinfunction "MP2_MP2") (pintype "passive"))
    )
    (net (code "151") (name "Net-(C363-Pad1)") (class "Default")
      (node (ref "C363") (pin "1") (pinfunction "1_1") (pintype "passive"))
      (node (ref "R89") (pin "2") (pinfunction "2_2") (pintype "passive"))
      (node (ref "R90") (pin "2") (pinfunction "2_2") (pintype "passive"))
      (node (ref "XS4") (pin "164") (pinfunction "164_164") (pintype "passive"))
    )
    (net (code "152") (name "Net-(C368-Pad1)") (class "Default")
      (node (ref "C368") (pin "1") (pinfunction "1_1") (pintype "passive"))
      (node (ref "R91") (pin "2") (pinfunction "2_2") (pintype "passive"))
      (node (ref "R92") (pin "2") (pinfunction "2_2") (pintype "passive"))
      (node (ref "XS4") (pin "258") (pinfunction "258_258") (pintype "passive"))
    )
    (net (code "153") (name "unconnected-(XS4-Pad87)") (class "Default")
      (node (ref "XS4") (pin "87") (pinfunction "87_87") (pintype "passive"))
    )
    (net (code "154") (name "unconnected-(XS4-Pad88)") (class "Default")
      (node (ref "XS4") (pin "88") (pinfunction "88_88") (pintype "passive"))
    )
    (net (code "155") (name "unconnected-(XS4-Pad91)") (class "Default")
      (node (ref "XS4") (pin "91") (pinfunction "91_91") (pintype "passive"))
    )
    (net (code "156") (name "unconnected-(XS4-Pad92)") (class "Default")
      (node (ref "XS4") (pin "92") (pinfunction "92_92") (pintype "passive"))
    )
    (net (code "157") (name "unconnected-(XS4-Pad95)") (class "Default")
      (node (ref "XS4") (pin "95") (pinfunction "95_95") (pintype "passive"))
    )
    (net (code "158") (name "unconnected-(XS4-Pad96)") (class "Default")
      (node (ref "XS4") (pin "96") (pinfunction "96_96") (pintype "passive"))
    )
    (net (code "159") (name "unconnected-(XS4-Pad97)") (class "Default")
      (node (ref "XS4") (pin "97") (pinfunction "97_97") (pintype "passive"))
    )
    (net (code "160") (name "unconnected-(XS4-Pad100)") (class "Default")
      (node (ref "XS4") (pin "100") (pinfunction "100_100") (pintype "passive"))
    )
    (net (code "161") (name "unconnected-(XS4-Pad101)") (class "Default")
      (node (ref "XS4") (pin "101") (pinfunction "101_101") (pintype "passive"))
    )
    (net (code "162") (name "unconnected-(XS4-Pad104)") (class "Default")
      (node (ref "XS4") (pin "104") (pinfunction "104_104") (pintype "passive"))
    )
    (net (code "163") (name "unconnected-(XS4-Pad105)") (class "Default")
      (node (ref "XS4") (pin "105") (pinfunction "105_105") (pintype "passive"))
    )
    (net (code "164") (name "unconnected-(XS4-Pad110)") (class "Default")
      (node (ref "XS4") (pin "110") (pinfunction "110_110") (pintype "passive"))
    )
    (net (code "165") (name "unconnected-(XS4-Pad134)") (class "Default")
      (node (ref "XS4") (pin "134") (pinfunction "134_134") (pintype "passive"))
    )
    (net (code "166") (name "unconnected-(XS4-Pad157)") (class "Default")
      (node (ref "XS4") (pin "157") (pinfunction "157_157") (pintype "passive"))
    )
    (net (code "167") (name "unconnected-(XS4-Pad161)") (class "Default")
      (node (ref "XS4") (pin "161") (pinfunction "161_161") (pintype "passive"))
    )
    (net (code "168") (name "unconnected-(XS4-Pad162)") (class "Default")
      (node (ref "XS4") (pin "162") (pinfunction "162_162") (pintype "passive"))
    )
    (net (code "169") (name "unconnected-(XS4-Pad165)") (class "Default")
      (node (ref "XS4") (pin "165") (pinfunction "165_165") (pintype "passive"))
    )
  )
)
